# Cart.net
KiCad netlist of a schematic drawn in Altium Designer
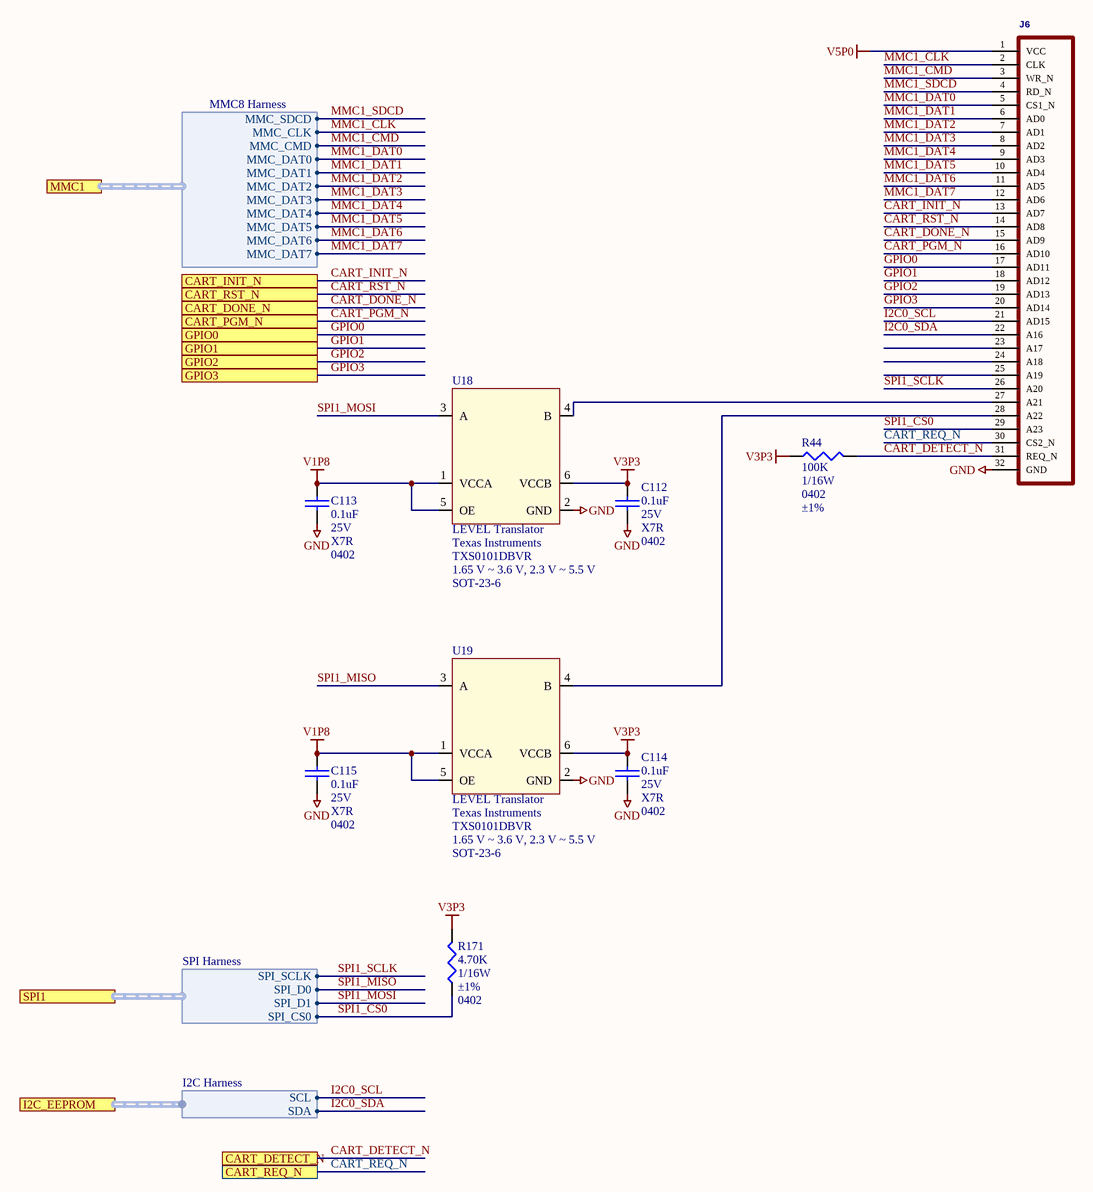
[diagram p0: Cart.SchDoc]

(export (version "E")
  (design (tool "Eeschema 10.0.6"))
  (components
    (comp (ref "C112")
      (value "C_0402_0.1UF_25V")
      (footprint "C_0402")
      (description "CAP CER 0.1UF 25V X6S 0402")
      (fields
        (field (name "TOLERANCE") "10%")
        (field (name "CAPACITANCE") "0.1uF")
        (field (name "VOLTAGE - RATED") "25V")
        (field (name "TEMPERATURE COEFFICIENT") "X7R")
        (field (name "PACKAGE / CASE") "0402")
      )
      (libsource (lib "Cospan Design") (part "C_0402_0.1UF_25V"))
    )
    (comp (ref "C113")
      (value "C_0402_0.1UF_25V")
      (footprint "C_0402")
      (description "CAP CER 0.1UF 25V X6S 0402")
      (fields
        (field (name "TOLERANCE") "10%")
        (field (name "CAPACITANCE") "0.1uF")
        (field (name "VOLTAGE - RATED") "25V")
        (field (name "TEMPERATURE COEFFICIENT") "X7R")
        (field (name "PACKAGE / CASE") "0402")
      )
      (libsource (lib "Cospan Design") (part "C_0402_0.1UF_25V"))
    )
    (comp (ref "C114")
      (value "C_0402_0.1UF_25V")
      (footprint "C_0402")
      (description "CAP CER 0.1UF 25V X6S 0402")
      (fields
        (field (name "TOLERANCE") "10%")
        (field (name "CAPACITANCE") "0.1uF")
        (field (name "VOLTAGE - RATED") "25V")
        (field (name "TEMPERATURE COEFFICIENT") "X7R")
        (field (name "PACKAGE / CASE") "0402")
      )
      (libsource (lib "Cospan Design") (part "C_0402_0.1UF_25V"))
    )
    (comp (ref "C115")
      (value "C_0402_0.1UF_25V")
      (footprint "C_0402")
      (description "CAP CER 0.1UF 25V X6S 0402")
      (fields
        (field (name "TOLERANCE") "10%")
        (field (name "CAPACITANCE") "0.1uF")
        (field (name "VOLTAGE - RATED") "25V")
        (field (name "TEMPERATURE COEFFICIENT") "X7R")
        (field (name "PACKAGE / CASE") "0402")
      )
      (libsource (lib "Cospan Design") (part "C_0402_0.1UF_25V"))
    )
    (comp (ref "J6")
      (value "GB_CART1")
      (footprint "GB_CART")
      (fields (field (name "LIBRARYNAME") "alex"))
      (libsource (lib "Cospan Design") (part "J_GB_CART"))
    )
    (comp (ref "R44")
      (value "R_0402_100K")
      (footprint "R_0402")
      (description "RES SMD 100K OHM 1% 1/16W 0402")
      (fields
        (field (name "MANUFACTURER") "Yageo")
        (field (name "MANUFACTURER PART NUMBER") "RC0402FR-07100KL")
        (field (name "RESISTANCE IN OHMS") "100K")
        (field (name "POWER (WATTS)") "1/16W")
        (field (name "CASE") "0402")
        (field (name "TOLERANCE") "±1%")
      )
      (libsource (lib "Cospan Design") (part "R_0402_100K"))
    )
    (comp (ref "R171")
      (value "4.7k Ohms")
      (footprint "R_0402")
      (description "RES 4.70K OHM 1/16W 1% 0402 SMD")
      (fields
        (field (name "MANUFACTURER") "Yageo")
        (field (name "MANUFACTURER PART NUMBER") "RC0402FR-074K7L")
        (field (name "RESISTANCE IN OHMS") "4.70K")
        (field (name "POWER (WATTS)") "1/16W")
        (field (name "TOLERANCE") "±1%")
        (field (name "CASE") "0402")
      )
      (libsource (lib "Main Library") (part "R_0402_4.70K"))
    )
    (comp (ref "U18")
      (value "LEVEL Translator")
      (footprint "TSOT-6")
      (description "IC V-LEVEL TRANSL BI-DIR SOT23-6")
      (fields
        (field (name "MANUFACTURER") "Texas Instruments")
        (field (name "MANUFACTURER PART NUMBER") "TXS0101DBVR")
        (field (name "VOLTAGE - SUPPLY") "1.65 V ~ 3.6 V, 2.3 V ~ 5.5 V")
        (field (name "PACKAGE / CASE") "SOT-23-6")
      )
      (libsource (lib "Main Library") (part "U_TXS0101DBVR"))
    )
    (comp (ref "U19")
      (value "LEVEL Translator")
      (footprint "TSOT-6")
      (description "IC V-LEVEL TRANSL BI-DIR SOT23-6")
      (fields
        (field (name "MANUFACTURER") "Texas Instruments")
        (field (name "MANUFACTURER PART NUMBER") "TXS0101DBVR")
        (field (name "VOLTAGE - SUPPLY") "1.65 V ~ 3.6 V, 2.3 V ~ 5.5 V")
        (field (name "PACKAGE / CASE") "SOT-23-6")
      )
      (libsource (lib "Main Library") (part "U_TXS0101DBVR"))
    )
  )
  (nets
    (net (code "5") (name "/CART_DETECT_N") (class "Default")
      (node (ref "J6") (pin "31") (pinfunction "REQ_N_31") (pintype "passive"))
      (node (ref "R44") (pin "1") (pinfunction "1_1") (pintype "passive"))
    )
    (net (code "6") (name "/CART_DONE_N") (class "Default")
      (node (ref "J6") (pin "15") (pinfunction "AD9_15") (pintype "passive"))
    )
    (net (code "7") (name "/CART_INIT_N") (class "Default")
      (node (ref "J6") (pin "13") (pinfunction "AD7_13") (pintype "passive"))
    )
    (net (code "8") (name "/CART_PGM_N") (class "Default")
      (node (ref "J6") (pin "16") (pinfunction "AD10_16") (pintype "passive"))
    )
    (net (code "9") (name "/CART_REQ_N") (class "Default")
      (node (ref "J6") (pin "30") (pinfunction "CS2_N_30") (pintype "passive"))
    )
    (net (code "10") (name "/CART_RST_N") (class "Default")
      (node (ref "J6") (pin "14") (pinfunction "AD8_14") (pintype "passive"))
    )
    (net (code "11") (name "/GPIO0") (class "Default")
      (node (ref "J6") (pin "17") (pinfunction "AD11_17") (pintype "passive"))
    )
    (net (code "12") (name "/GPIO1") (class "Default")
      (node (ref "J6") (pin "18") (pinfunction "AD12_18") (pintype "passive"))
    )
    (net (code "13") (name "/GPIO2") (class "Default")
      (node (ref "J6") (pin "19") (pinfunction "AD13_19") (pintype "passive"))
    )
    (net (code "14") (name "/GPIO3") (class "Default")
      (node (ref "J6") (pin "20") (pinfunction "AD14_20") (pintype "passive"))
    )
    (net (code "15") (name "/I2C0_SCL") (class "Default")
      (node (ref "J6") (pin "21") (pinfunction "AD15_21") (pintype "passive"))
    )
    (net (code "16") (name "/I2C0_SDA") (class "Default")
      (node (ref "J6") (pin "22") (pinfunction "A16_22") (pintype "passive"))
    )
    (net (code "17") (name "/MMC1_CLK") (class "Default")
      (node (ref "J6") (pin "2") (pinfunction "CLK_2") (pintype "passive"))
    )
    (net (code "18") (name "/MMC1_CMD") (class "Default")
      (node (ref "J6") (pin "3") (pinfunction "WR_N_3") (pintype "passive"))
    )
    (net (code "19") (name "/MMC1_DAT0") (class "Default")
      (node (ref "J6") (pin "5") (pinfunction "CS1_N_5") (pintype "passive"))
    )
    (net (code "20") (name "/MMC1_DAT1") (class "Default")
      (node (ref "J6") (pin "6") (pinfunction "AD0_6") (pintype "passive"))
    )
    (net (code "21") (name "/MMC1_DAT2") (class "Default")
      (node (ref "J6") (pin "7") (pinfunction "AD1_7") (pintype "passive"))
    )
    (net (code "22") (name "/MMC1_DAT3") (class "Default")
      (node (ref "J6") (pin "8") (pinfunction "AD2_8") (pintype "passive"))
    )
    (net (code "23") (name "/MMC1_DAT4") (class "Default")
      (node (ref "J6") (pin "9") (pinfunction "AD3_9") (pintype "passive"))
    )
    (net (code "24") (name "/MMC1_DAT5") (class "Default")
      (node (ref "J6") (pin "10") (pinfunction "AD4_10") (pintype "passive"))
    )
    (net (code "25") (name "/MMC1_DAT6") (class "Default")
      (node (ref "J6") (pin "11") (pinfunction "AD5_11") (pintype "passive"))
    )
    (net (code "26") (name "/MMC1_DAT7") (class "Default")
      (node (ref "J6") (pin "12") (pinfunction "AD6_12") (pintype "passive"))
    )
    (net (code "27") (name "/MMC1_SDCD") (class "Default")
      (node (ref "J6") (pin "4") (pinfunction "RD_N_4") (pintype "passive"))
    )
    (net (code "28") (name "/SPI1_CS0") (class "Default")
      (node (ref "J6") (pin "29") (pinfunction "A23_29") (pintype "passive"))
      (node (ref "R171") (pin "2") (pinfunction "2_2") (pintype "passive"))
    )
    (net (code "29") (name "/SPI1_MISO") (class "Default")
      (node (ref "U19") (pin "3") (pinfunction "A_3") (pintype "passive"))
    )
    (net (code "30") (name "/SPI1_MOSI") (class "Default")
      (node (ref "U18") (pin "3") (pinfunction "A_3") (pintype "passive"))
    )
    (net (code "31") (name "/SPI1_SCLK") (class "Default")
      (node (ref "J6") (pin "26") (pinfunction "A20_26") (pintype "passive"))
    )
    (net (code "35") (name "GND") (class "Default")
      (node (ref "C112") (pin "1") (pinfunction "1_1") (pintype "passive"))
      (node (ref "C113") (pin "1") (pinfunction "1_1") (pintype "passive"))
      (node (ref "C114") (pin "1") (pinfunction "1_1") (pintype "passive"))
      (node (ref "C115") (pin "1") (pinfunction "1_1") (pintype "passive"))
      (node (ref "J6") (pin "32") (pinfunction "GND_32") (pintype "passive"))
      (node (ref "U18") (pin "2") (pinfunction "GND_2") (pintype "passive"))
      (node (ref "U19") (pin "2") (pinfunction "GND_2") (pintype "passive"))
    )
    (net (code "36") (name "Net-(J6-A21)") (class "Default")
      (node (ref "J6") (pin "27") (pinfunction "A21_27") (pintype "passive"))
      (node (ref "U18") (pin "4") (pinfunction "B_4") (pintype "passive"))
    )
    (net (code "37") (name "Net-(J6-A22)") (class "Default")
      (node (ref "J6") (pin "28") (pinfunction "A22_28") (pintype "passive"))
      (node (ref "U19") (pin "4") (pinfunction "B_4") (pintype "passive"))
    )
    (net (code "38") (name "V1P8") (class "Default")
      (node (ref "C113") (pin "2") (pinfunction "2_2") (pintype "passive"))
      (node (ref "C115") (pin "2") (pinfunction "2_2") (pintype "passive"))
      (node (ref "U18") (pin "1") (pinfunction "VCCA_1") (pintype "passive"))
      (node (ref "U18") (pin "5") (pinfunction "OE_5") (pintype "passive"))
      (node (ref "U19") (pin "1") (pinfunction "VCCA_1") (pintype "passive"))
      (node (ref "U19") (pin "5") (pinfunction "OE_5") (pintype "passive"))
    )
    (net (code "39") (name "V3P3") (class "Default")
      (node (ref "C112") (pin "2") (pinfunction "2_2") (pintype "passive"))
      (node (ref "C114") (pin "2") (pinfunction "2_2") (pintype "passive"))
      (node (ref "R171") (pin "1") (pinfunction "1_1") (pintype "passive"))
      (node (ref "R44") (pin "2") (pinfunction "2_2") (pintype "passive"))
      (node (ref "U18") (pin "6") (pinfunction "VCCB_6") (pintype "passive"))
      (node (ref "U19") (pin "6") (pinfunction "VCCB_6") (pintype "passive"))
    )
    (net (code "40") (name "V5P0") (class "Default")
      (node (ref "J6") (pin "1") (pinfunction "VCC_1") (pintype "passive"))
    )
    (net (code "41") (name "unconnected-(J6-A17-Pad23)") (class "Default")
      (node (ref "J6") (pin "23") (pinfunction "A17_23") (pintype "passive"))
    )
    (net (code "42") (name "unconnected-(J6-A18-Pad24)") (class "Default")
      (node (ref "J6") (pin "24") (pinfunction "A18_24") (pintype "passive"))
    )
    (net (code "43") (name "unconnected-(J6-A19-Pad25)") (class "Default")
      (node (ref "J6") (pin "25") (pinfunction "A19_25") (pintype "passive"))
    )
  )
)
